# CAN.net
KiCad netlist of a schematic drawn in Altium Designer
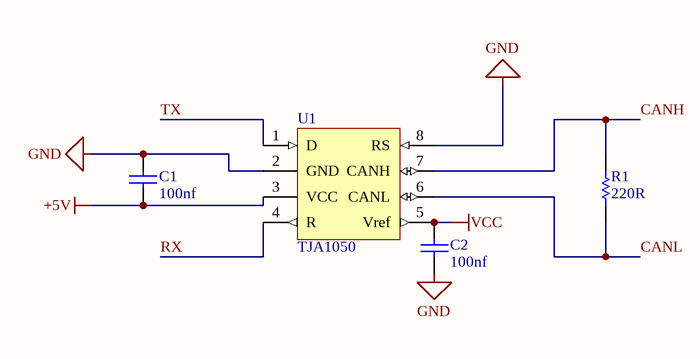
[diagram p0: CAN.SchDoc]

(export (version "E")
  (design (tool "Eeschema 10.0.6"))
  (components
    (comp (ref "C1")
      (value "100nf")
      (footprint "0603-1")
      (description "Capacitor")
      (fields (field (name "PUBLISHER") "Altium Limited"))
      (libsource (lib "My Footprint") (part "CAP"))
    )
    (comp (ref "C2")
      (value "100nf")
      (footprint "0603-1")
      (description "Capacitor")
      (fields (field (name "PUBLISHER") "Altium Limited"))
      (libsource (lib "My Footprint") (part "CAP"))
    )
    (comp (ref "R1")
      (value "220R")
      (footprint "0603-1")
      (description "Resistor")
      (fields (field (name "PUBLISHER") "Altium Limited"))
      (libsource (lib "My Footprint") (part "RES"))
    )
    (comp (ref "U1")
      (value "TJA1050")
      (footprint "SOP8-TJA1050")
      (libsource (lib "My Footprint") (part "TJA1050"))
    )
  )
  (nets
    (net (code "1") (name "+5V") (class "Default")
      (node (ref "C1") (pin "1") (pinfunction "1_1") (pintype "passive"))
      (node (ref "U1") (pin "3") (pinfunction "VCC_3") (pintype "passive"))
    )
    (net (code "2") (name "/CANH") (class "Default")
      (node (ref "R1") (pin "2") (pinfunction "2_2") (pintype "passive"))
      (node (ref "U1") (pin "7") (pinfunction "CANH_7") (pintype "bidirectional"))
    )
    (net (code "3") (name "/CANL") (class "Default")
      (node (ref "R1") (pin "1") (pinfunction "1_1") (pintype "passive"))
      (node (ref "U1") (pin "6") (pinfunction "CANL_6") (pintype "bidirectional"))
    )
    (net (code "4") (name "/RX") (class "Default")
      (node (ref "U1") (pin "4") (pinfunction "R_4") (pintype "output"))
    )
    (net (code "5") (name "/TX") (class "Default")
      (node (ref "U1") (pin "1") (pinfunction "D_1") (pintype "input"))
    )
    (net (code "6") (name "GND") (class "Default")
      (node (ref "C1") (pin "2") (pinfunction "2_2") (pintype "passive"))
      (node (ref "C2") (pin "2") (pinfunction "2_2") (pintype "passive"))
      (node (ref "U1") (pin "2") (pinfunction "GND_2") (pintype "passive"))
      (node (ref "U1") (pin "8") (pinfunction "RS_8") (pintype "input"))
    )
    (net (code "7") (name "VCC") (class "Default")
      (node (ref "C2") (pin "1") (pinfunction "1_1") (pintype "passive"))
      (node (ref "U1") (pin "5") (pinfunction "Vref_5") (pintype "output"))
    )
  )
)
